# hexbot.net
KiCad netlist of a schematic drawn in Altium Designer
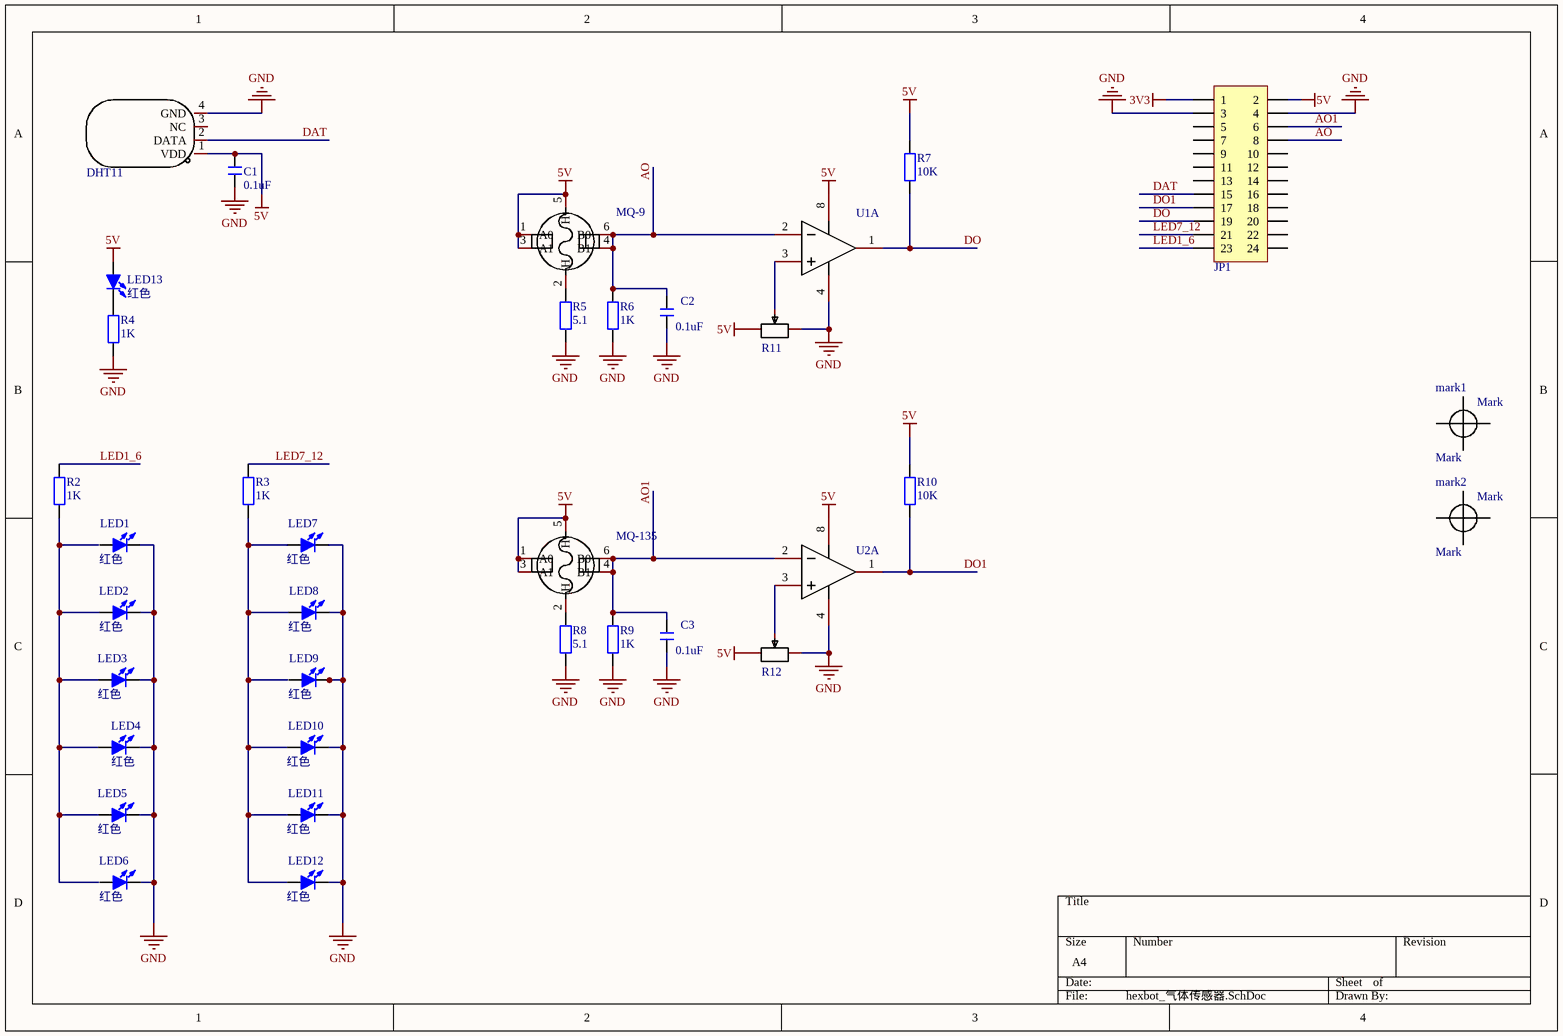
[diagram p0: hexbot_气体传感器.SchDoc]

(export (version "E")
  (design (tool "Eeschema 10.0.6"))
  (components
    (comp (ref "C1")
      (value "0.1uF")
      (footprint "C 0603_L")
      (description "贴片电容")
      (libsource (lib "0.1 - 电阻-电容-电感") (part "C"))
    )
    (comp (ref "C2")
      (value "0.1uF")
      (footprint "C 0603_L")
      (description "贴片电容")
      (libsource (lib "0.1 - 电阻-电容-电感") (part "C"))
    )
    (comp (ref "C3")
      (value "0.1uF")
      (footprint "C 0603_L")
      (description "贴片电容")
      (libsource (lib "0.1 - 电阻-电容-电感") (part "C"))
    )
    (comp (ref "DHT11")
      (value "DHT11")
      (footprint "DHT11")
      (description "传感器类型:Humidity, Temperature;输出类型:-;温度范围:-;湿度范围:-;精度:-;")
      (fields (field (name "MANUFACTURER") "广州奥松"))
      (libsource (lib "DHT11") (part "DHT11"))
    )
    (comp (ref "JP1")
      (value "Header 2X11")
      (footprint "HDR2.54-WI-2x12P")
      (description "12*2P接插件")
      (fields (field (name "版权归属") "封装库来自淘宝卖家 ID：黄晶宝石"))
      (libsource (lib "5.4 - 接插件-脚距2.54 (100mil) ") (part "Header 12X2"))
    )
    (comp (ref "LED1")
      (value "红色")
      (footprint "LED 0603R")
      (description "贴片LED")
      (fields (field (name "版权归属") "封装库来自淘宝 ID：黄晶宝石"))
      (libsource (lib "0.3 - LED发光二极管") (part "LED-SMD"))
    )
    (comp (ref "LED2")
      (value "红色")
      (footprint "LED 0603R")
      (description "贴片LED")
      (fields (field (name "版权归属") "封装库来自淘宝 ID：黄晶宝石"))
      (libsource (lib "0.3 - LED发光二极管") (part "LED-SMD"))
    )
    (comp (ref "LED3")
      (value "红色")
      (footprint "LED 0603R")
      (description "贴片LED")
      (fields (field (name "版权归属") "封装库来自淘宝 ID：黄晶宝石"))
      (libsource (lib "0.3 - LED发光二极管") (part "LED-SMD"))
    )
    (comp (ref "LED4")
      (value "红色")
      (footprint "LED 0603R")
      (description "贴片LED")
      (fields (field (name "版权归属") "封装库来自淘宝 ID：黄晶宝石"))
      (libsource (lib "0.3 - LED发光二极管") (part "LED-SMD"))
    )
    (comp (ref "LED5")
      (value "红色")
      (footprint "LED 0603R")
      (description "贴片LED")
      (fields (field (name "版权归属") "封装库来自淘宝 ID：黄晶宝石"))
      (libsource (lib "0.3 - LED发光二极管") (part "LED-SMD"))
    )
    (comp (ref "LED6")
      (value "红色")
      (footprint "LED 0603R")
      (description "贴片LED")
      (fields (field (name "版权归属") "封装库来自淘宝 ID：黄晶宝石"))
      (libsource (lib "0.3 - LED发光二极管") (part "LED-SMD"))
    )
    (comp (ref "LED7")
      (value "红色")
      (footprint "LED 0603R")
      (description "贴片LED")
      (fields (field (name "版权归属") "封装库来自淘宝 ID：黄晶宝石"))
      (libsource (lib "0.3 - LED发光二极管") (part "LED-SMD"))
    )
    (comp (ref "LED8")
      (value "红色")
      (footprint "LED 0603R")
      (description "贴片LED")
      (fields (field (name "版权归属") "封装库来自淘宝 ID：黄晶宝石"))
      (libsource (lib "0.3 - LED发光二极管") (part "LED-SMD"))
    )
    (comp (ref "LED9")
      (value "红色")
      (footprint "LED 0603R")
      (description "贴片LED")
      (fields (field (name "版权归属") "封装库来自淘宝 ID：黄晶宝石"))
      (libsource (lib "0.3 - LED发光二极管") (part "LED-SMD"))
    )
    (comp (ref "LED10")
      (value "红色")
      (footprint "LED 0603R")
      (description "贴片LED")
      (fields (field (name "版权归属") "封装库来自淘宝 ID：黄晶宝石"))
      (libsource (lib "0.3 - LED发光二极管") (part "LED-SMD"))
    )
    (comp (ref "LED11")
      (value "红色")
      (footprint "LED 0603R")
      (description "贴片LED")
      (fields (field (name "版权归属") "封装库来自淘宝 ID：黄晶宝石"))
      (libsource (lib "0.3 - LED发光二极管") (part "LED-SMD"))
    )
    (comp (ref "LED12")
      (value "红色")
      (footprint "LED 0603R")
      (description "贴片LED")
      (fields (field (name "版权归属") "封装库来自淘宝 ID：黄晶宝石"))
      (libsource (lib "0.3 - LED发光二极管") (part "LED-SMD"))
    )
    (comp (ref "LED13")
      (value "红色")
      (footprint "LED 0603R")
      (description "贴片LED")
      (fields (field (name "版权归属") "封装库来自淘宝 ID：黄晶宝石"))
      (libsource (lib "0.3 - LED发光二极管") (part "LED-SMD"))
    )
    (comp (ref "mark1") (value "Mark") (footprint "Mark:Mark") (libsource (lib "Mark") (part "Mark")))
    (comp (ref "mark2") (value "Mark") (footprint "Mark:Mark") (libsource (lib "Mark") (part "Mark")))
    (comp (ref "MQ-9")
      (value "MQ-9")
      (footprint "MQ")
      (description "MQ-4天燃气检测传感器，与MQ-2特性")
      (fields (field (name "MANUFACTURER") "Winsen(炜盛)") (field (name "MANUFACTURER PART") "MQ-4"))
      (libsource (lib "MQ") (part "MQ-4"))
    )
    (comp (ref "MQ-135")
      (value "MQ-9")
      (footprint "MQ")
      (description "MQ-4天燃气检测传感器，与MQ-2特性")
      (fields (field (name "MANUFACTURER") "Winsen(炜盛)") (field (name "MANUFACTURER PART") "MQ-4"))
      (libsource (lib "MQ") (part "MQ-4"))
    )
    (comp (ref "R2")
      (value "1K")
      (footprint "R 0603_L")
      (description "贴片电阻")
      (fields (field (name "版权归属") "来自淘宝 ID：黄晶宝石"))
      (libsource (lib "0.1 - 电阻-电容-电感") (part "R"))
    )
    (comp (ref "R3")
      (value "1K")
      (footprint "R 0603_L")
      (description "贴片电阻")
      (fields (field (name "版权归属") "来自淘宝 ID：黄晶宝石"))
      (libsource (lib "0.1 - 电阻-电容-电感") (part "R"))
    )
    (comp (ref "R4")
      (value "1K")
      (footprint "R 0603_L")
      (description "贴片电阻")
      (fields (field (name "版权归属") "来自淘宝 ID：黄晶宝石"))
      (libsource (lib "0.1 - 电阻-电容-电感") (part "R"))
    )
    (comp (ref "R5")
      (value "5.1")
      (footprint "R 0603_L")
      (description "贴片电阻")
      (fields (field (name "版权归属") "来自淘宝 ID：黄晶宝石"))
      (libsource (lib "0.1 - 电阻-电容-电感") (part "R"))
    )
    (comp (ref "R6")
      (value "1K")
      (footprint "R 0603_L")
      (description "贴片电阻")
      (fields (field (name "版权归属") "来自淘宝 ID：黄晶宝石"))
      (libsource (lib "0.1 - 电阻-电容-电感") (part "R"))
    )
    (comp (ref "R7")
      (value "10K")
      (footprint "R 0603_L")
      (description "贴片电阻")
      (fields (field (name "版权归属") "来自淘宝 ID：黄晶宝石"))
      (libsource (lib "0.1 - 电阻-电容-电感") (part "R"))
    )
    (comp (ref "R8")
      (value "5.1")
      (footprint "R 0603_L")
      (description "贴片电阻")
      (fields (field (name "版权归属") "来自淘宝 ID：黄晶宝石"))
      (libsource (lib "0.1 - 电阻-电容-电感") (part "R"))
    )
    (comp (ref "R9")
      (value "1K")
      (footprint "R 0603_L")
      (description "贴片电阻")
      (fields (field (name "版权归属") "来自淘宝 ID：黄晶宝石"))
      (libsource (lib "0.1 - 电阻-电容-电感") (part "R"))
    )
    (comp (ref "R10")
      (value "10K")
      (footprint "R 0603_L")
      (description "贴片电阻")
      (fields (field (name "版权归属") "来自淘宝 ID：黄晶宝石"))
      (libsource (lib "0.1 - 电阻-电容-电感") (part "R"))
    )
    (comp (ref "R11")
      (value "RM065-V1-103")
      (footprint "RM065")
      (description "精度:±20%;")
      (libsource (lib "RM065") (part "RM065-V1-103"))
    )
    (comp (ref "R12")
      (value "RM065-V1-103")
      (footprint "RM065")
      (description "精度:±20%;")
      (libsource (lib "RM065") (part "RM065-V1-103"))
    )
    (comp (ref "U1")
      (value "LM393")
      (footprint "LM393")
      (description "比较器组数:-;电源电压:-;各通道供电电流:-;输出类型:-;传播延迟:-;")
      (fields (field (name "MANUFACTURER") "IDCHIP(英锐芯)"))
      (libsource (lib "LM393") (part "LM393"))
    )
    (comp (ref "U2")
      (value "LM393")
      (footprint "LM393")
      (description "比较器组数:-;电源电压:-;各通道供电电流:-;输出类型:-;传播延迟:-;")
      (fields (field (name "MANUFACTURER") "IDCHIP(英锐芯)"))
      (libsource (lib "LM393") (part "LM393"))
    )
  )
  (nets
    (net (code "1") (name "/AO") (class "Default")
      (node (ref "C2") (pin "2") (pinfunction "2_2") (pintype "passive"))
      (node (ref "JP1") (pin "8") (pinfunction "8_8") (pintype "passive"))
      (node (ref "MQ-9") (pin "4") (pinfunction "B1_4") (pintype "passive"))
      (node (ref "MQ-9") (pin "6") (pinfunction "B0_6") (pintype "passive"))
      (node (ref "R6") (pin "2") (pinfunction "2_2") (pintype "passive"))
      (node (ref "U1") (pin "2") (pinfunction "INA-_2") (pintype "passive"))
    )
    (net (code "2") (name "/AO1") (class "Default")
      (node (ref "C3") (pin "2") (pinfunction "2_2") (pintype "passive"))
      (node (ref "JP1") (pin "6") (pinfunction "6_6") (pintype "passive"))
      (node (ref "MQ-135") (pin "4") (pinfunction "B1_4") (pintype "passive"))
      (node (ref "MQ-135") (pin "6") (pinfunction "B0_6") (pintype "passive"))
      (node (ref "R9") (pin "2") (pinfunction "2_2") (pintype "passive"))
      (node (ref "U2") (pin "2") (pinfunction "INA-_2") (pintype "passive"))
    )
    (net (code "3") (name "/DAT") (class "Default")
      (node (ref "DHT11") (pin "2") (pinfunction "DATA_2") (pintype "passive"))
      (node (ref "JP1") (pin "15") (pinfunction "15_15") (pintype "passive"))
    )
    (net (code "4") (name "/DO") (class "Default")
      (node (ref "JP1") (pin "19") (pinfunction "19_19") (pintype "passive"))
      (node (ref "R7") (pin "1") (pinfunction "1_1") (pintype "passive"))
      (node (ref "U1") (pin "1") (pinfunction "OUTA_1") (pintype "passive"))
    )
    (net (code "5") (name "/DO1") (class "Default")
      (node (ref "JP1") (pin "17") (pinfunction "17_17") (pintype "passive"))
      (node (ref "R10") (pin "1") (pinfunction "1_1") (pintype "passive"))
      (node (ref "U2") (pin "1") (pinfunction "OUTA_1") (pintype "passive"))
    )
    (net (code "6") (name "/LED1_6") (class "Default")
      (node (ref "JP1") (pin "23") (pinfunction "23_23") (pintype "passive"))
      (node (ref "R2") (pin "2") (pinfunction "2_2") (pintype "passive"))
    )
    (net (code "7") (name "/LED7_12") (class "Default")
      (node (ref "JP1") (pin "21") (pinfunction "21_21") (pintype "passive"))
      (node (ref "R3") (pin "2") (pinfunction "2_2") (pintype "passive"))
    )
    (net (code "8") (name "3V3") (class "Default")
      (node (ref "JP1") (pin "1") (pinfunction "1_1") (pintype "passive"))
    )
    (net (code "9") (name "5V") (class "Default")
      (node (ref "C1") (pin "2") (pinfunction "2_2") (pintype "passive"))
      (node (ref "DHT11") (pin "1") (pinfunction "VDD_1") (pintype "passive"))
      (node (ref "JP1") (pin "2") (pinfunction "2_2") (pintype "passive"))
      (node (ref "LED13") (pin "1") (pinfunction "A_1") (pintype "passive"))
      (node (ref "MQ-135") (pin "1") (pinfunction "A0_1") (pintype "passive"))
      (node (ref "MQ-135") (pin "3") (pinfunction "A1_3") (pintype "passive"))
      (node (ref "MQ-135") (pin "5") (pinfunction "H_5") (pintype "passive"))
      (node (ref "MQ-9") (pin "1") (pinfunction "A0_1") (pintype "passive"))
      (node (ref "MQ-9") (pin "3") (pinfunction "A1_3") (pintype "passive"))
      (node (ref "MQ-9") (pin "5") (pinfunction "H_5") (pintype "passive"))
      (node (ref "R10") (pin "2") (pinfunction "2_2") (pintype "passive"))
      (node (ref "R11") (pin "1") (pinfunction "1_1") (pintype "passive"))
      (node (ref "R12") (pin "1") (pinfunction "1_1") (pintype "passive"))
      (node (ref "R7") (pin "2") (pinfunction "2_2") (pintype "passive"))
      (node (ref "U1") (pin "8") (pinfunction "VCC_8") (pintype "passive"))
      (node (ref "U2") (pin "8") (pinfunction "VCC_8") (pintype "passive"))
    )
    (net (code "10") (name "GND") (class "Default")
      (node (ref "C1") (pin "1") (pinfunction "1_1") (pintype "passive"))
      (node (ref "C2") (pin "1") (pinfunction "1_1") (pintype "passive"))
      (node (ref "C3") (pin "1") (pinfunction "1_1") (pintype "passive"))
      (node (ref "DHT11") (pin "4") (pinfunction "GND_4") (pintype "passive"))
      (node (ref "JP1") (pin "3") (pinfunction "3_3") (pintype "passive"))
      (node (ref "JP1") (pin "4") (pinfunction "4_4") (pintype "passive"))
      (node (ref "LED1") (pin "2") (pinfunction "K_2") (pintype "passive"))
      (node (ref "LED10") (pin "2") (pinfunction "K_2") (pintype "passive"))
      (node (ref "LED11") (pin "2") (pinfunction "K_2") (pintype "passive"))
      (node (ref "LED12") (pin "2") (pinfunction "K_2") (pintype "passive"))
      (node (ref "LED2") (pin "2") (pinfunction "K_2") (pintype "passive"))
      (node (ref "LED3") (pin "2") (pinfunction "K_2") (pintype "passive"))
      (node (ref "LED4") (pin "2") (pinfunction "K_2") (pintype "passive"))
      (node (ref "LED5") (pin "2") (pinfunction "K_2") (pintype "passive"))
      (node (ref "LED6") (pin "2") (pinfunction "K_2") (pintype "passive"))
      (node (ref "LED7") (pin "2") (pinfunction "K_2") (pintype "passive"))
      (node (ref "LED8") (pin "2") (pinfunction "K_2") (pintype "passive"))
      (node (ref "LED9") (pin "2") (pinfunction "K_2") (pintype "passive"))
      (node (ref "R11") (pin "3") (pinfunction "3_3") (pintype "passive"))
      (node (ref "R12") (pin "3") (pinfunction "3_3") (pintype "passive"))
      (node (ref "R4") (pin "1") (pinfunction "1_1") (pintype "passive"))
      (node (ref "R5") (pin "1") (pinfunction "1_1") (pintype "passive"))
      (node (ref "R6") (pin "1") (pinfunction "1_1") (pintype "passive"))
      (node (ref "R8") (pin "1") (pinfunction "1_1") (pintype "passive"))
      (node (ref "R9") (pin "1") (pinfunction "1_1") (pintype "passive"))
      (node (ref "U1") (pin "4") (pinfunction "GND_4") (pintype "passive"))
      (node (ref "U2") (pin "4") (pinfunction "GND_4") (pintype "passive"))
    )
    (net (code "11") (name "Net-(LED2-A)") (class "Default")
      (node (ref "LED2") (pin "1") (pinfunction "A_1") (pintype "passive"))
      (node (ref "LED3") (pin "1") (pinfunction "A_1") (pintype "passive"))
      (node (ref "LED4") (pin "1") (pinfunction "A_1") (pintype "passive"))
      (node (ref "LED5") (pin "1") (pinfunction "A_1") (pintype "passive"))
      (node (ref "R2") (pin "1") (pinfunction "1_1") (pintype "passive"))
    )
    (net (code "12") (name "Net-(LED10-A)") (class "Default")
      (node (ref "LED10") (pin "1") (pinfunction "A_1") (pintype "passive"))
      (node (ref "LED11") (pin "1") (pinfunction "A_1") (pintype "passive"))
      (node (ref "LED12") (pin "1") (pinfunction "A_1") (pintype "passive"))
      (node (ref "LED7") (pin "1") (pinfunction "A_1") (pintype "passive"))
      (node (ref "LED8") (pin "1") (pinfunction "A_1") (pintype "passive"))
      (node (ref "R3") (pin "1") (pinfunction "1_1") (pintype "passive"))
    )
    (net (code "13") (name "Net-(LED13-K)") (class "Default")
      (node (ref "LED13") (pin "2") (pinfunction "K_2") (pintype "passive"))
      (node (ref "R4") (pin "2") (pinfunction "2_2") (pintype "passive"))
    )
    (net (code "14") (name "Net-(MQ-9-H-Pad2)") (class "Default")
      (node (ref "MQ-9") (pin "2") (pinfunction "H_2") (pintype "passive"))
      (node (ref "R5") (pin "2") (pinfunction "2_2") (pintype "passive"))
    )
    (net (code "15") (name "Net-(MQ-135-H-Pad2)") (class "Default")
      (node (ref "MQ-135") (pin "2") (pinfunction "H_2") (pintype "passive"))
      (node (ref "R8") (pin "2") (pinfunction "2_2") (pintype "passive"))
    )
    (net (code "16") (name "Net-(U1A-INA+)") (class "Default")
      (node (ref "R11") (pin "2") (pinfunction "2_2") (pintype "passive"))
      (node (ref "U1") (pin "3") (pinfunction "INA+_3") (pintype "passive"))
    )
    (net (code "17") (name "Net-(U2A-INA+)") (class "Default")
      (node (ref "R12") (pin "2") (pinfunction "2_2") (pintype "passive"))
      (node (ref "U2") (pin "3") (pinfunction "INA+_3") (pintype "passive"))
    )
    (net (code "18") (name "unconnected-(DHT11-NC-Pad3)") (class "Default")
      (node (ref "DHT11") (pin "3") (pinfunction "NC_3") (pintype "passive"))
    )
    (net (code "19") (name "unconnected-(JP1-Pad5)") (class "Default")
      (node (ref "JP1") (pin "5") (pinfunction "5_5") (pintype "passive"))
    )
    (net (code "20") (name "unconnected-(JP1-Pad7)") (class "Default")
      (node (ref "JP1") (pin "7") (pinfunction "7_7") (pintype "passive"))
    )
    (net (code "21") (name "unconnected-(JP1-Pad9)") (class "Default")
      (node (ref "JP1") (pin "9") (pinfunction "9_9") (pintype "passive"))
    )
    (net (code "22") (name "unconnected-(JP1-Pad10)") (class "Default")
      (node (ref "JP1") (pin "10") (pinfunction "10_10") (pintype "passive"))
    )
    (net (code "23") (name "unconnected-(JP1-Pad11)") (class "Default")
      (node (ref "JP1") (pin "11") (pinfunction "11_11") (pintype "passive"))
    )
    (net (code "24") (name "unconnected-(JP1-Pad12)") (class "Default")
      (node (ref "JP1") (pin "12") (pinfunction "12_12") (pintype "passive"))
    )
    (net (code "25") (name "unconnected-(JP1-Pad13)") (class "Default")
      (node (ref "JP1") (pin "13") (pinfunction "13_13") (pintype "passive"))
    )
    (net (code "26") (name "unconnected-(JP1-Pad14)") (class "Default")
      (node (ref "JP1") (pin "14") (pinfunction "14_14") (pintype "passive"))
    )
    (net (code "27") (name "unconnected-(JP1-Pad16)") (class "Default")
      (node (ref "JP1") (pin "16") (pinfunction "16_16") (pintype "passive"))
    )
    (net (code "28") (name "unconnected-(JP1-Pad18)") (class "Default")
      (node (ref "JP1") (pin "18") (pinfunction "18_18") (pintype "passive"))
    )
    (net (code "29") (name "unconnected-(JP1-Pad20)") (class "Default")
      (node (ref "JP1") (pin "20") (pinfunction "20_20") (pintype "passive"))
    )
    (net (code "30") (name "unconnected-(JP1-Pad22)") (class "Default")
      (node (ref "JP1") (pin "22") (pinfunction "22_22") (pintype "passive"))
    )
    (net (code "31") (name "unconnected-(JP1-Pad24)") (class "Default")
      (node (ref "JP1") (pin "24") (pinfunction "24_24") (pintype "passive"))
    )
    (net (code "32") (name "unconnected-(LED1-A-Pad1)") (class "Default")
      (node (ref "LED1") (pin "1") (pinfunction "A_1") (pintype "passive"))
    )
    (net (code "33") (name "unconnected-(LED6-A-Pad1)") (class "Default")
      (node (ref "LED6") (pin "1") (pinfunction "A_1") (pintype "passive"))
    )
    (net (code "34") (name "unconnected-(LED9-A-Pad1)") (class "Default")
      (node (ref "LED9") (pin "1") (pinfunction "A_1") (pintype "passive"))
    )
  )
)
